# e3_tp2_ej2.net
KiCad netlist of a schematic drawn in Altium Designer
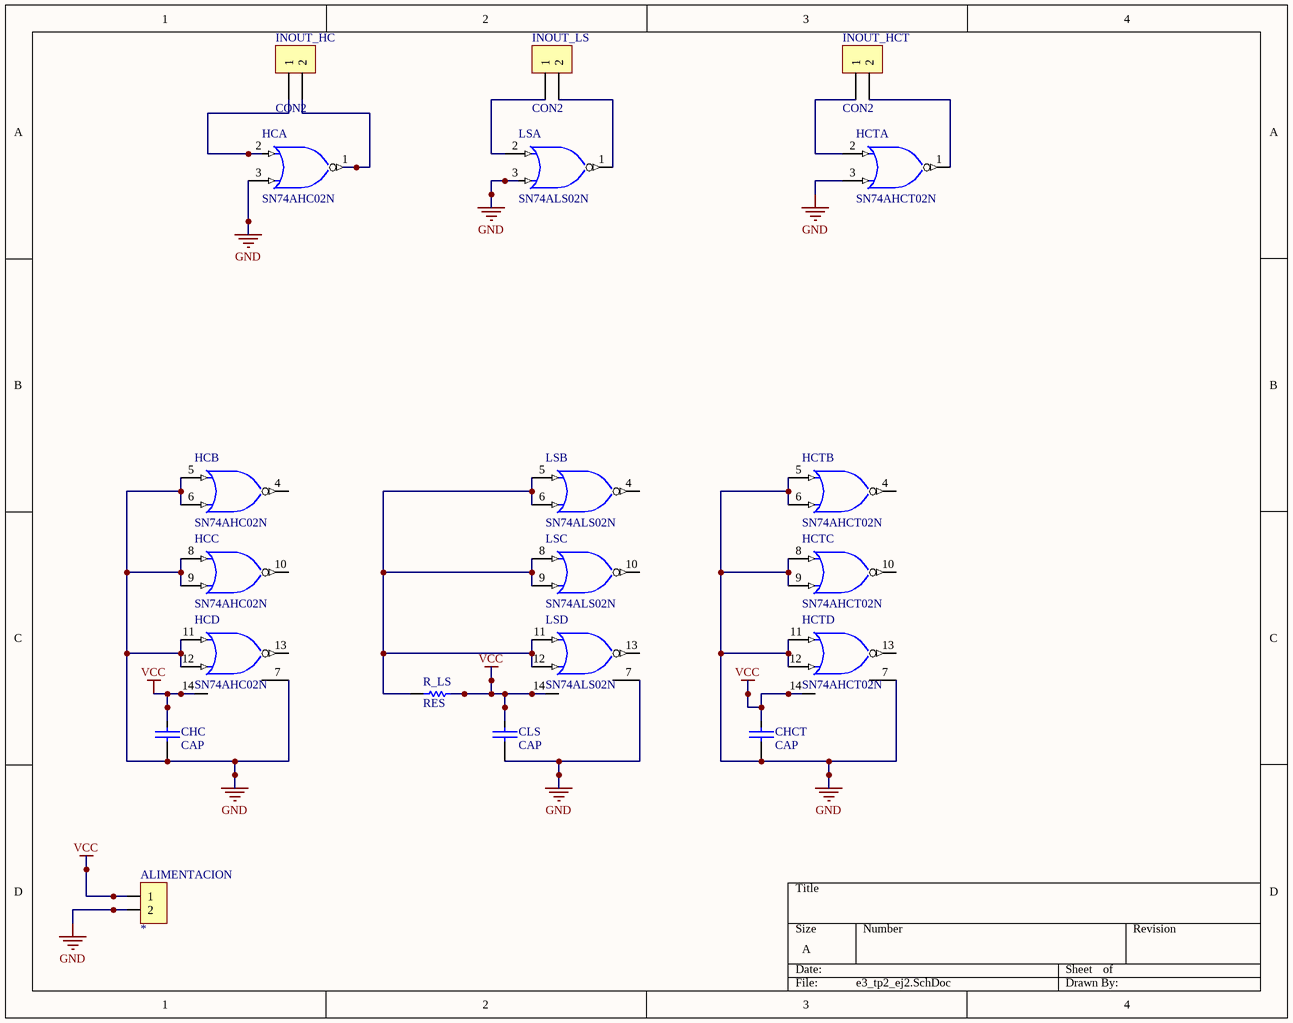
[diagram p0: e3_tp2_ej2.SchDoc]

(export (version "E")
  (design (tool "Eeschema 10.0.6"))
  (components
    (comp (ref "ALIMENTACION") (value "*") (footprint "SIP2") (libsource (lib "LIBEBAL") (part "CON2")))
    (comp (ref "CHC") (value "CAP") (footprint "CAP200") (libsource (lib "LIBEBAL") (part "CAP")))
    (comp (ref "CHCT") (value "CAP") (footprint "CAP200") (libsource (lib "LIBEBAL") (part "CAP")))
    (comp (ref "CLS") (value "CAP") (footprint "CAP200") (libsource (lib "LIBEBAL") (part "CAP")))
    (comp (ref "HC")
      (value "SN74AHC02N")
      (footprint "N014")
      (description "Quadruple 2-Input Positive-NOR Gate")
      (fields (field (name "PUBLISHER") "Altium Limited"))
      (libsource (lib "TI Logic Gate 1") (part "SN74AHC02N"))
    )
    (comp (ref "HCT")
      (value "SN74AHCT02N")
      (footprint "N014")
      (description "Quadruple 2-Input Positive-NOR Gate")
      (fields (field (name "PUBLISHER") "Altium Limited"))
      (libsource (lib "TI Logic Gate 1") (part "SN74AHCT02N"))
    )
    (comp (ref "INOUT_HC") (value "CON2") (footprint "SIP2") (libsource (lib "") (part "CON2_1")))
    (comp (ref "INOUT_HCT") (value "CON2") (footprint "SIP2") (libsource (lib "") (part "CON2_1")))
    (comp (ref "INOUT_LS") (value "CON2") (footprint "SIP2") (libsource (lib "") (part "CON2_1")))
    (comp (ref "LS")
      (value "SN74ALS02N")
      (footprint "N014")
      (description "Quadruple 2-Input Positive-NOR Gate")
      (fields (field (name "PUBLISHER") "Altium Limited"))
      (libsource (lib "TI Logic Gate 1") (part "SN74ALS02N"))
    )
    (comp (ref "R_LS") (value "RES") (footprint "RES300") (libsource (lib "LIBEBAL") (part "RES")))
  )
  (nets
    (net (code "1") (name "GND") (class "Default")
      (node (ref "ALIMENTACION") (pin "2") (pinfunction "2_2") (pintype "passive"))
      (node (ref "CHC") (pin "2") (pinfunction "2_2") (pintype "passive"))
      (node (ref "CHCT") (pin "2") (pinfunction "2_2") (pintype "passive"))
      (node (ref "CLS") (pin "2") (pinfunction "2_2") (pintype "passive"))
      (node (ref "HC") (pin "11") (pinfunction "A_11") (pintype "input"))
      (node (ref "HC") (pin "12") (pinfunction "B_12") (pintype "input"))
      (node (ref "HC") (pin "3") (pinfunction "B_3") (pintype "input"))
      (node (ref "HC") (pin "5") (pinfunction "A_5") (pintype "input"))
      (node (ref "HC") (pin "6") (pinfunction "B_6") (pintype "input"))
      (node (ref "HC") (pin "7") (pinfunction "GND_7") (pintype "power_in"))
      (node (ref "HC") (pin "8") (pinfunction "A_8") (pintype "input"))
      (node (ref "HC") (pin "9") (pinfunction "B_9") (pintype "input"))
      (node (ref "HCT") (pin "11") (pinfunction "A_11") (pintype "input"))
      (node (ref "HCT") (pin "12") (pinfunction "B_12") (pintype "input"))
      (node (ref "HCT") (pin "3") (pinfunction "B_3") (pintype "input"))
      (node (ref "HCT") (pin "5") (pinfunction "A_5") (pintype "input"))
      (node (ref "HCT") (pin "6") (pinfunction "B_6") (pintype "input"))
      (node (ref "HCT") (pin "7") (pinfunction "GND_7") (pintype "power_in"))
      (node (ref "HCT") (pin "8") (pinfunction "A_8") (pintype "input"))
      (node (ref "HCT") (pin "9") (pinfunction "B_9") (pintype "input"))
      (node (ref "LS") (pin "3") (pinfunction "B_3") (pintype "input"))
      (node (ref "LS") (pin "7") (pinfunction "GND_7") (pintype "power_in"))
    )
    (net (code "2") (name "Net-(HCA-A)") (class "Default")
      (node (ref "HC") (pin "2") (pinfunction "A_2") (pintype "input"))
      (node (ref "INOUT_HC") (pin "1") (pinfunction "1_1") (pintype "passive"))
    )
    (net (code "3") (name "Net-(HCA-Y)") (class "Default")
      (node (ref "HC") (pin "1") (pinfunction "Y_1") (pintype "output"))
      (node (ref "INOUT_HC") (pin "2") (pinfunction "2_2") (pintype "passive"))
    )
    (net (code "4") (name "Net-(HCTA-A)") (class "Default")
      (node (ref "HCT") (pin "2") (pinfunction "A_2") (pintype "input"))
      (node (ref "INOUT_HCT") (pin "1") (pinfunction "1_1") (pintype "passive"))
    )
    (net (code "5") (name "Net-(HCTA-Y)") (class "Default")
      (node (ref "HCT") (pin "1") (pinfunction "Y_1") (pintype "output"))
      (node (ref "INOUT_HCT") (pin "2") (pinfunction "2_2") (pintype "passive"))
    )
    (net (code "6") (name "Net-(LSA-A)") (class "Default")
      (node (ref "INOUT_LS") (pin "1") (pinfunction "1_1") (pintype "passive"))
      (node (ref "LS") (pin "2") (pinfunction "A_2") (pintype "input"))
    )
    (net (code "7") (name "Net-(LSA-Y)") (class "Default")
      (node (ref "INOUT_LS") (pin "2") (pinfunction "2_2") (pintype "passive"))
      (node (ref "LS") (pin "1") (pinfunction "Y_1") (pintype "output"))
    )
    (net (code "8") (name "Net-(LSB-A)") (class "Default")
      (node (ref "LS") (pin "11") (pinfunction "A_11") (pintype "input"))
      (node (ref "LS") (pin "12") (pinfunction "B_12") (pintype "input"))
      (node (ref "LS") (pin "5") (pinfunction "A_5") (pintype "input"))
      (node (ref "LS") (pin "6") (pinfunction "B_6") (pintype "input"))
      (node (ref "LS") (pin "8") (pinfunction "A_8") (pintype "input"))
      (node (ref "LS") (pin "9") (pinfunction "B_9") (pintype "input"))
      (node (ref "R_LS") (pin "1") (pinfunction "1_1") (pintype "passive"))
    )
    (net (code "9") (name "VCC") (class "Default")
      (node (ref "ALIMENTACION") (pin "1") (pinfunction "1_1") (pintype "passive"))
      (node (ref "CHC") (pin "1") (pinfunction "1_1") (pintype "passive"))
      (node (ref "CHCT") (pin "1") (pinfunction "1_1") (pintype "passive"))
      (node (ref "CLS") (pin "1") (pinfunction "1_1") (pintype "passive"))
      (node (ref "HC") (pin "14") (pinfunction "VCC_14") (pintype "power_in"))
      (node (ref "HCT") (pin "14") (pinfunction "VCC_14") (pintype "power_in"))
      (node (ref "LS") (pin "14") (pinfunction "VCC_14") (pintype "power_in"))
      (node (ref "R_LS") (pin "2") (pinfunction "2_2") (pintype "passive"))
    )
    (net (code "10") (name "unconnected-(HCB-Y-Pad4)") (class "Default")
      (node (ref "HC") (pin "4") (pinfunction "Y_4") (pintype "output"))
    )
    (net (code "11") (name "unconnected-(HCC-Y-Pad10)") (class "Default")
      (node (ref "HC") (pin "10") (pinfunction "Y_10") (pintype "output"))
    )
    (net (code "12") (name "unconnected-(HCD-Y-Pad13)") (class "Default")
      (node (ref "HC") (pin "13") (pinfunction "Y_13") (pintype "output"))
    )
    (net (code "13") (name "unconnected-(HCTB-Y-Pad4)") (class "Default")
      (node (ref "HCT") (pin "4") (pinfunction "Y_4") (pintype "output"))
    )
    (net (code "14") (name "unconnected-(HCTC-Y-Pad10)") (class "Default")
      (node (ref "HCT") (pin "10") (pinfunction "Y_10") (pintype "output"))
    )
    (net (code "15") (name "unconnected-(HCTD-Y-Pad13)") (class "Default")
      (node (ref "HCT") (pin "13") (pinfunction "Y_13") (pintype "output"))
    )
    (net (code "16") (name "unconnected-(LSB-Y-Pad4)") (class "Default")
      (node (ref "LS") (pin "4") (pinfunction "Y_4") (pintype "output"))
    )
    (net (code "17") (name "unconnected-(LSC-Y-Pad10)") (class "Default")
      (node (ref "LS") (pin "10") (pinfunction "Y_10") (pintype "output"))
    )
    (net (code "18") (name "unconnected-(LSD-Y-Pad13)") (class "Default")
      (node (ref "LS") (pin "13") (pinfunction "Y_13") (pintype "output"))
    )
  )
)
